# stepper_control_board.net
KiCad netlist of a schematic drawn in EAGLE
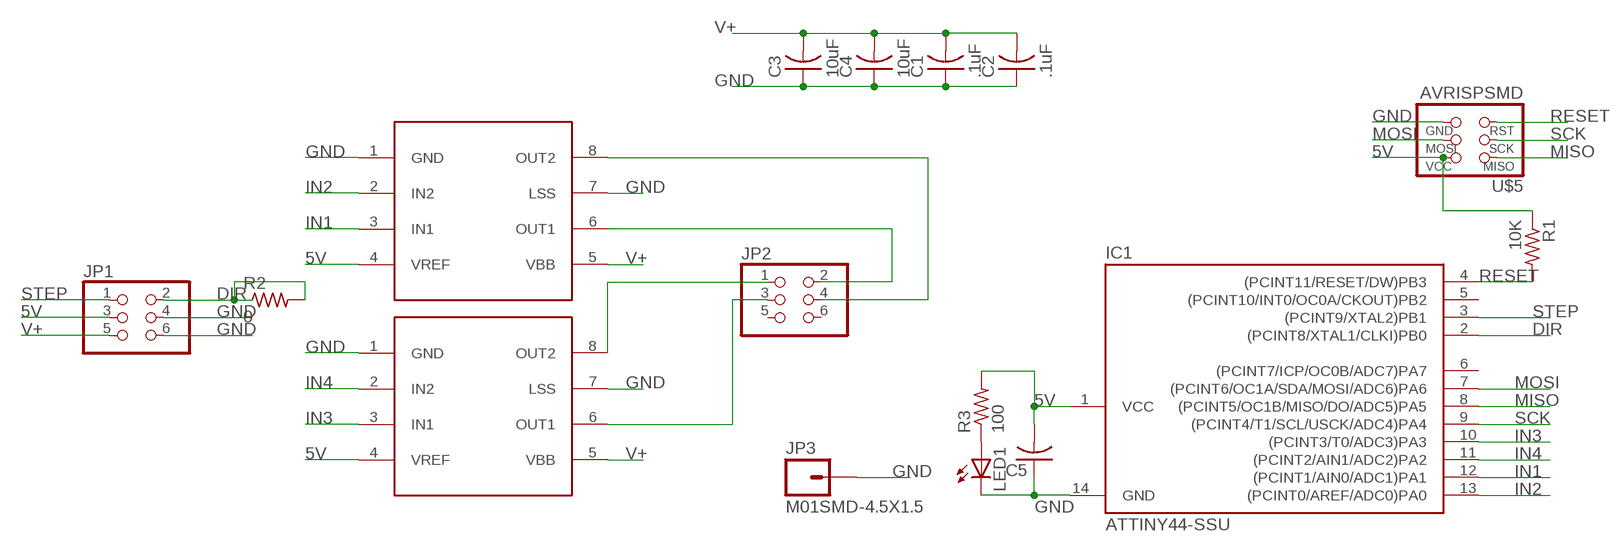
[diagram p0: schematic, sheet 1]

(export (version "E")
  (design (tool "Eeschema 10.0.6"))
  (components
    (comp (ref "C1")
      (value ".1uF")
      (footprint "eagle-import:C1206FAB")
      (libsource (lib "eagle-import") (part "CAP-US1206FAB"))
    )
    (comp (ref "C2")
      (value ".1uF")
      (footprint "eagle-import:C1206FAB")
      (libsource (lib "eagle-import") (part "CAP-US1206FAB"))
    )
    (comp (ref "C3")
      (value "10uF")
      (footprint "eagle-import:C1206FAB")
      (libsource (lib "eagle-import") (part "CAP-US1206FAB"))
    )
    (comp (ref "C4")
      (value "10uF")
      (footprint "eagle-import:C1206FAB")
      (libsource (lib "eagle-import") (part "CAP-US1206FAB"))
    )
    (comp (ref "C5")
      (value "C-USC1206")
      (footprint "eagle-import:C1206")
      (libsource (lib "eagle-import") (part "C-USC1206"))
    )
    (comp (ref "IC1")
      (value "ATTINY44-SSU")
      (footprint "eagle-import:SOIC14")
      (libsource (lib "eagle-import") (part "ATTINY44-SSU"))
    )
    (comp (ref "JP1")
      (value "PINHD-2X3-SMD")
      (footprint "eagle-import:2X03SMD")
      (libsource (lib "eagle-import") (part "PINHD-2X3-SMD"))
    )
    (comp (ref "JP2")
      (value "PINHD-2X3-SMD")
      (footprint "eagle-import:2X03SMD")
      (libsource (lib "eagle-import") (part "PINHD-2X3-SMD"))
    )
    (comp (ref "JP3")
      (value "M01SMD-4.5X1.5")
      (footprint "eagle-import:PAD-1.5X4.5")
      (libsource (lib "eagle-import") (part "M01SMD-4.5X1.5"))
    )
    (comp (ref "LED1")
      (value "LED1206")
      (footprint "eagle-import:LED-1206")
      (libsource (lib "eagle-import") (part "LED1206"))
    )
    (comp (ref "R1")
      (value "10K")
      (footprint "eagle-import:R1206FAB")
      (libsource (lib "eagle-import") (part "RES-US1206FAB"))
    )
    (comp (ref "R2")
      (value "0")
      (footprint "eagle-import:R1206FAB")
      (libsource (lib "eagle-import") (part "RES-US1206FAB"))
    )
    (comp (ref "R3")
      (value "100")
      (footprint "eagle-import:R1206FAB")
      (libsource (lib "eagle-import") (part "RES-US1206FAB"))
    )
    (comp (ref "U$1")
      (value "A4953-H-BRIDGE-MOTOR-DRIVER")
      (footprint "eagle-import:SOIC8")
      (libsource (lib "eagle-import") (part "A4953-H-BRIDGE-MOTOR-DRIVER"))
    )
    (comp (ref "U$2")
      (value "A4953-H-BRIDGE-MOTOR-DRIVER")
      (footprint "eagle-import:SOIC8")
      (libsource (lib "eagle-import") (part "A4953-H-BRIDGE-MOTOR-DRIVER"))
    )
    (comp (ref "U$5")
      (value "AVRISPSMD")
      (footprint "eagle-import:2X03SMD")
      (libsource (lib "eagle-import") (part "AVRISPSMD"))
    )
  )
  (nets
    (net (code "1") (name "/5V") (class "Default")
      (node (ref "C5") (pin "2") (pinfunction "2_2") (pintype "passive"))
      (node (ref "IC1") (pin "1") (pinfunction "VCC_1") (pintype "power_in"))
      (node (ref "JP1") (pin "3") (pinfunction "3_3") (pintype "passive"))
      (node (ref "R1") (pin "1") (pinfunction "1_1") (pintype "passive"))
      (node (ref "R3") (pin "2") (pinfunction "2_2") (pintype "passive"))
      (node (ref "U$1") (pin "4") (pinfunction "VREF_4") (pintype "bidirectional"))
      (node (ref "U$2") (pin "4") (pinfunction "VREF_4") (pintype "bidirectional"))
      (node (ref "U$5") (pin "2") (pinfunction "VCC_2") (pintype "passive"))
    )
    (net (code "2") (name "/DIR") (class "Default")
      (node (ref "IC1") (pin "2") (pinfunction "(PCINT8/XTAL1/CLKI)PB0_2") (pintype "bidirectional"))
      (node (ref "JP1") (pin "2") (pinfunction "2_2") (pintype "passive"))
      (node (ref "R2") (pin "1") (pinfunction "1_1") (pintype "passive"))
      (node (ref "R2") (pin "2") (pinfunction "2_2") (pintype "passive"))
    )
    (net (code "3") (name "/GND") (class "Default")
      (node (ref "C1") (pin "1") (pinfunction "1_1") (pintype "passive"))
      (node (ref "C2") (pin "1") (pinfunction "1_1") (pintype "passive"))
      (node (ref "C3") (pin "1") (pinfunction "1_1") (pintype "passive"))
      (node (ref "C4") (pin "1") (pinfunction "1_1") (pintype "passive"))
      (node (ref "C5") (pin "1") (pinfunction "1_1") (pintype "passive"))
      (node (ref "IC1") (pin "14") (pinfunction "GND_14") (pintype "power_in"))
      (node (ref "JP1") (pin "4") (pinfunction "4_4") (pintype "passive"))
      (node (ref "JP1") (pin "6") (pinfunction "6_6") (pintype "passive"))
      (node (ref "JP3") (pin "P$1") (pinfunction "1_P$1") (pintype "passive"))
      (node (ref "LED1") (pin "C") (pinfunction "C_C") (pintype "passive"))
      (node (ref "U$1") (pin "1") (pinfunction "GND_1") (pintype "bidirectional"))
      (node (ref "U$1") (pin "7") (pinfunction "LSS_7") (pintype "bidirectional"))
      (node (ref "U$2") (pin "1") (pinfunction "GND_1") (pintype "bidirectional"))
      (node (ref "U$2") (pin "7") (pinfunction "LSS_7") (pintype "bidirectional"))
      (node (ref "U$5") (pin "6") (pinfunction "GND_6") (pintype "passive"))
    )
    (net (code "4") (name "/IN1") (class "Default")
      (node (ref "IC1") (pin "12") (pinfunction "(PCINT1/AIN0/ADC1)PA1_12") (pintype "bidirectional"))
      (node (ref "U$1") (pin "3") (pinfunction "IN1_3") (pintype "bidirectional"))
    )
    (net (code "5") (name "/IN2") (class "Default")
      (node (ref "IC1") (pin "13") (pinfunction "(PCINT0/AREF/ADC0)PA0_13") (pintype "bidirectional"))
      (node (ref "U$1") (pin "2") (pinfunction "IN2_2") (pintype "bidirectional"))
    )
    (net (code "6") (name "/IN3") (class "Default")
      (node (ref "IC1") (pin "10") (pinfunction "(PCINT3/T0/ADC3)PA3_10") (pintype "bidirectional"))
      (node (ref "U$2") (pin "3") (pinfunction "IN1_3") (pintype "bidirectional"))
    )
    (net (code "7") (name "/IN4") (class "Default")
      (node (ref "IC1") (pin "11") (pinfunction "(PCINT2/AIN1/ADC2)PA2_11") (pintype "bidirectional"))
      (node (ref "U$2") (pin "2") (pinfunction "IN2_2") (pintype "bidirectional"))
    )
    (net (code "8") (name "/MISO") (class "Default")
      (node (ref "IC1") (pin "8") (pinfunction "(PCINT5/OC1B/MISO/DO/ADC5)PA5_8") (pintype "bidirectional"))
      (node (ref "U$5") (pin "1") (pinfunction "MISO_1") (pintype "passive"))
    )
    (net (code "9") (name "/MOSI") (class "Default")
      (node (ref "IC1") (pin "7") (pinfunction "(PCINT6/OC1A/SDA/MOSI/ADC6)PA6_7") (pintype "bidirectional"))
      (node (ref "U$5") (pin "4") (pinfunction "MOSI_4") (pintype "passive"))
    )
    (net (code "10") (name "/RESET") (class "Default")
      (node (ref "IC1") (pin "4") (pinfunction "(PCINT11/RESET/DW)PB3_4") (pintype "bidirectional"))
      (node (ref "R1") (pin "2") (pinfunction "2_2") (pintype "passive"))
      (node (ref "U$5") (pin "5") (pinfunction "RST_5") (pintype "passive"))
    )
    (net (code "11") (name "/SCK") (class "Default")
      (node (ref "IC1") (pin "9") (pinfunction "(PCINT4/T1/SCL/USCK/ADC4)PA4_9") (pintype "bidirectional"))
      (node (ref "U$5") (pin "3") (pinfunction "SCK_3") (pintype "passive"))
    )
    (net (code "12") (name "/STEP") (class "Default")
      (node (ref "IC1") (pin "3") (pinfunction "(PCINT9/XTAL2)PB1_3") (pintype "bidirectional"))
      (node (ref "JP1") (pin "1") (pinfunction "1_1") (pintype "passive"))
    )
    (net (code "13") (name "/V+") (class "Default")
      (node (ref "C1") (pin "2") (pinfunction "2_2") (pintype "passive"))
      (node (ref "C2") (pin "2") (pinfunction "2_2") (pintype "passive"))
      (node (ref "C3") (pin "2") (pinfunction "2_2") (pintype "passive"))
      (node (ref "C4") (pin "2") (pinfunction "2_2") (pintype "passive"))
      (node (ref "JP1") (pin "5") (pinfunction "5_5") (pintype "passive"))
      (node (ref "U$1") (pin "5") (pinfunction "VBB_5") (pintype "bidirectional"))
      (node (ref "U$2") (pin "5") (pinfunction "VBB_5") (pintype "bidirectional"))
    )
    (net (code "14") (name "Net-(LED1-PadA)") (class "Default")
      (node (ref "LED1") (pin "A") (pinfunction "A_A") (pintype "passive"))
      (node (ref "R3") (pin "1") (pinfunction "1_1") (pintype "passive"))
    )
    (net (code "15") (name "Net-(U$1-OUT1)") (class "Default")
      (node (ref "JP2") (pin "2") (pinfunction "2_2") (pintype "passive"))
      (node (ref "U$1") (pin "6") (pinfunction "OUT1_6") (pintype "bidirectional"))
    )
    (net (code "16") (name "Net-(U$1-OUT2)") (class "Default")
      (node (ref "JP2") (pin "4") (pinfunction "4_4") (pintype "passive"))
      (node (ref "U$1") (pin "8") (pinfunction "OUT2_8") (pintype "bidirectional"))
    )
    (net (code "17") (name "Net-(U$2-OUT1)") (class "Default")
      (node (ref "JP2") (pin "3") (pinfunction "3_3") (pintype "passive"))
      (node (ref "U$2") (pin "6") (pinfunction "OUT1_6") (pintype "bidirectional"))
    )
    (net (code "18") (name "Net-(U$2-OUT2)") (class "Default")
      (node (ref "JP2") (pin "1") (pinfunction "1_1") (pintype "passive"))
      (node (ref "U$2") (pin "8") (pinfunction "OUT2_8") (pintype "bidirectional"))
    )
    (net (code "19") (name "unconnected-(IC1-(PCINT7{slash}ICP{slash}OC0B{slash}ADC7)PA7-Pad6)") (class "Default")
      (node (ref "IC1") (pin "6") (pinfunction "(PCINT7/ICP/OC0B/ADC7)PA7_6") (pintype "bidirectional"))
    )
    (net (code "20") (name "unconnected-(IC1-(PCINT10{slash}INT0{slash}OC0A{slash}CKOUT)PB2-Pad5)") (class "Default")
      (node (ref "IC1") (pin "5") (pinfunction "(PCINT10/INT0/OC0A/CKOUT)PB2_5") (pintype "bidirectional"))
    )
    (net (code "21") (name "unconnected-(JP2-Pad5)") (class "Default")
      (node (ref "JP2") (pin "5") (pinfunction "5_5") (pintype "passive"))
    )
    (net (code "22") (name "unconnected-(JP2-Pad6)") (class "Default")
      (node (ref "JP2") (pin "6") (pinfunction "6_6") (pintype "passive"))
    )
  )
)
